# 1_8-TFT-128x160.net
KiCad netlist of a schematic drawn in Altium Designer
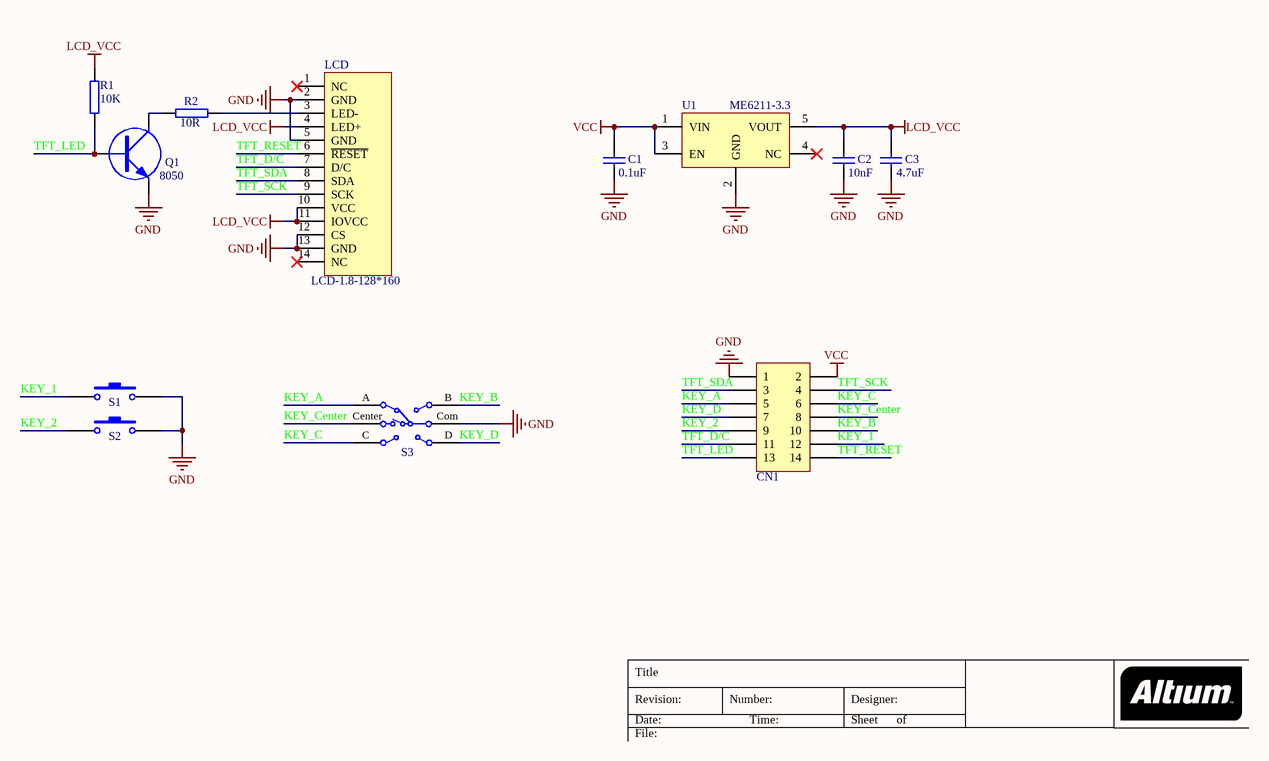
[diagram p0: 1.8-TFT-128x160.SchDoc]

(export (version "E")
  (design (tool "Eeschema 10.0.6"))
  (components
    (comp (ref "C1") (value "0.1uF") (footprint "CAP-0603") (libsource (lib "Connectors") (part "Cap")))
    (comp (ref "C2") (value "10nF") (footprint "CAP-0603") (libsource (lib "Connectors") (part "Cap")))
    (comp (ref "C3") (value "4.7uF") (footprint "CAP-0603") (libsource (lib "Connectors") (part "Cap")))
    (comp (ref "CN1")
      (value "CON-7X2")
      (footprint "Pin-Header-2.00-Straight_SMD-14")
      (libsource (lib "Connectors-Header") (part "CON-7X2"))
    )
    (comp (ref "LCD")
      (value "LCD-1.8-128*160")
      (footprint "LCD-1.8-128*160-14P")
      (libsource (lib "Devices") (part "LCD-1.8-128*160-14P"))
    )
    (comp (ref "Q1") (value "8050") (footprint "SOT-23-3") (libsource (lib "Devices") (part "NPN")))
    (comp (ref "R1") (value "10K") (footprint "RES-0603") (libsource (lib "Connectors") (part "Res")))
    (comp (ref "R2") (value "10R") (footprint "RES-0603") (libsource (lib "Connectors") (part "Res")))
    (comp (ref "S1") (value "Key") (footprint "SW-PB-2") (libsource (lib "Connectors") (part "Key-PB-2")))
    (comp (ref "S2") (value "Key") (footprint "SW-PB-2") (libsource (lib "Connectors") (part "Key-PB-2")))
    (comp (ref "S3")
      (value "Switch")
      (footprint "SW-ALPS-5")
      (libsource (lib "Connectors") (part "Switch-ALPS-5"))
    )
    (comp (ref "U1")
      (value "ME6211-3.3")
      (footprint "SOT-23-5")
      (fields (field (name "PUBLISHER") "Altium Limited"))
      (libsource (lib "Devices") (part "LDO"))
    )
  )
  (nets
    (net (code "1") (name "/KEY_1") (class "Default")
      (node (ref "CN1") (pin "12") (pinfunction "12_12") (pintype "passive"))
      (node (ref "S1") (pin "1") (pinfunction "1_1") (pintype "passive"))
    )
    (net (code "2") (name "/KEY_2") (class "Default")
      (node (ref "CN1") (pin "9") (pinfunction "9_9") (pintype "passive"))
      (node (ref "S2") (pin "1") (pinfunction "1_1") (pintype "passive"))
    )
    (net (code "3") (name "/KEY_A") (class "Default")
      (node (ref "CN1") (pin "5") (pinfunction "5_5") (pintype "passive"))
      (node (ref "S3") (pin "1") (pinfunction "1_1") (pintype "passive"))
    )
    (net (code "4") (name "/KEY_B") (class "Default")
      (node (ref "CN1") (pin "10") (pinfunction "10_10") (pintype "passive"))
      (node (ref "S3") (pin "4") (pinfunction "4_4") (pintype "passive"))
    )
    (net (code "5") (name "/KEY_C") (class "Default")
      (node (ref "CN1") (pin "6") (pinfunction "6_6") (pintype "passive"))
      (node (ref "S3") (pin "3") (pinfunction "3_3") (pintype "passive"))
    )
    (net (code "6") (name "/KEY_Center") (class "Default")
      (node (ref "CN1") (pin "8") (pinfunction "8_8") (pintype "passive"))
      (node (ref "S3") (pin "2") (pinfunction "2_2") (pintype "passive"))
    )
    (net (code "7") (name "/KEY_D") (class "Default")
      (node (ref "CN1") (pin "7") (pinfunction "7_7") (pintype "passive"))
      (node (ref "S3") (pin "6") (pinfunction "6_6") (pintype "passive"))
    )
    (net (code "8") (name "/TFT_D{slash}C") (class "Default")
      (node (ref "CN1") (pin "11") (pinfunction "11_11") (pintype "passive"))
      (node (ref "LCD") (pin "7") (pinfunction "D/C_7") (pintype "passive"))
    )
    (net (code "9") (name "/TFT_LED") (class "Default")
      (node (ref "CN1") (pin "13") (pinfunction "13_13") (pintype "passive"))
      (node (ref "Q1") (pin "1") (pinfunction "B_1") (pintype "passive"))
      (node (ref "R1") (pin "1") (pinfunction "1_1") (pintype "passive"))
    )
    (net (code "10") (name "/TFT_RESET") (class "Default")
      (node (ref "CN1") (pin "14") (pinfunction "14_14") (pintype "passive"))
      (node (ref "LCD") (pin "6") (pinfunction "~{RESET}_6") (pintype "passive"))
    )
    (net (code "11") (name "/TFT_SCK") (class "Default")
      (node (ref "CN1") (pin "4") (pinfunction "4_4") (pintype "passive"))
      (node (ref "LCD") (pin "9") (pinfunction "SCK_9") (pintype "passive"))
    )
    (net (code "12") (name "/TFT_SDA") (class "Default")
      (node (ref "CN1") (pin "3") (pinfunction "3_3") (pintype "passive"))
      (node (ref "LCD") (pin "8") (pinfunction "SDA_8") (pintype "passive"))
    )
    (net (code "13") (name "GND") (class "Default")
      (node (ref "C1") (pin "1") (pinfunction "1_1") (pintype "passive"))
      (node (ref "C2") (pin "1") (pinfunction "1_1") (pintype "passive"))
      (node (ref "C3") (pin "1") (pinfunction "1_1") (pintype "passive"))
      (node (ref "CN1") (pin "1") (pinfunction "1_1") (pintype "passive"))
      (node (ref "LCD") (pin "12") (pinfunction "CS_12") (pintype "passive"))
      (node (ref "LCD") (pin "13") (pinfunction "GND_13") (pintype "passive"))
      (node (ref "LCD") (pin "2") (pinfunction "GND_2") (pintype "passive"))
      (node (ref "LCD") (pin "5") (pinfunction "GND_5") (pintype "passive"))
      (node (ref "Q1") (pin "2") (pinfunction "E_2") (pintype "passive"))
      (node (ref "S1") (pin "2") (pinfunction "2_2") (pintype "passive"))
      (node (ref "S2") (pin "2") (pinfunction "2_2") (pintype "passive"))
      (node (ref "S3") (pin "5") (pinfunction "5_5") (pintype "passive"))
      (node (ref "U1") (pin "2") (pinfunction "GND_2") (pintype "passive"))
    )
    (net (code "14") (name "LCD_VCC") (class "Default")
      (node (ref "C2") (pin "2") (pinfunction "2_2") (pintype "passive"))
      (node (ref "C3") (pin "2") (pinfunction "2_2") (pintype "passive"))
      (node (ref "LCD") (pin "10") (pinfunction "VCC_10") (pintype "passive"))
      (node (ref "LCD") (pin "11") (pinfunction "IOVCC_11") (pintype "passive"))
      (node (ref "LCD") (pin "4") (pinfunction "LED+_4") (pintype "passive"))
      (node (ref "R1") (pin "2") (pinfunction "2_2") (pintype "passive"))
      (node (ref "U1") (pin "5") (pinfunction "VOUT_5") (pintype "passive"))
    )
    (net (code "15") (name "Net-(LCD-LED-)") (class "Default")
      (node (ref "LCD") (pin "3") (pinfunction "LED-_3") (pintype "passive"))
      (node (ref "R2") (pin "2") (pinfunction "2_2") (pintype "passive"))
    )
    (net (code "16") (name "Net-(Q1-C)") (class "Default")
      (node (ref "Q1") (pin "3") (pinfunction "C_3") (pintype "passive"))
      (node (ref "R2") (pin "1") (pinfunction "1_1") (pintype "passive"))
    )
    (net (code "17") (name "VCC") (class "Default")
      (node (ref "C1") (pin "2") (pinfunction "2_2") (pintype "passive"))
      (node (ref "CN1") (pin "2") (pinfunction "2_2") (pintype "passive"))
      (node (ref "U1") (pin "1") (pinfunction "VIN_1") (pintype "passive"))
      (node (ref "U1") (pin "3") (pinfunction "EN_3") (pintype "passive"))
    )
    (net (code "18") (name "unconnected-(LCD-NC-Pad1)") (class "Default")
      (node (ref "LCD") (pin "1") (pinfunction "NC_1") (pintype "passive+no_connect"))
    )
    (net (code "19") (name "unconnected-(LCD-NC-Pad14)") (class "Default")
      (node (ref "LCD") (pin "14") (pinfunction "NC_14") (pintype "passive+no_connect"))
    )
    (net (code "20") (name "unconnected-(U1-NC-Pad4)") (class "Default")
      (node (ref "U1") (pin "4") (pinfunction "NC_4") (pintype "passive+no_connect"))
    )
  )
)
